# Sheet_1.net
KiCad netlist of a schematic drawn in Altium Designer
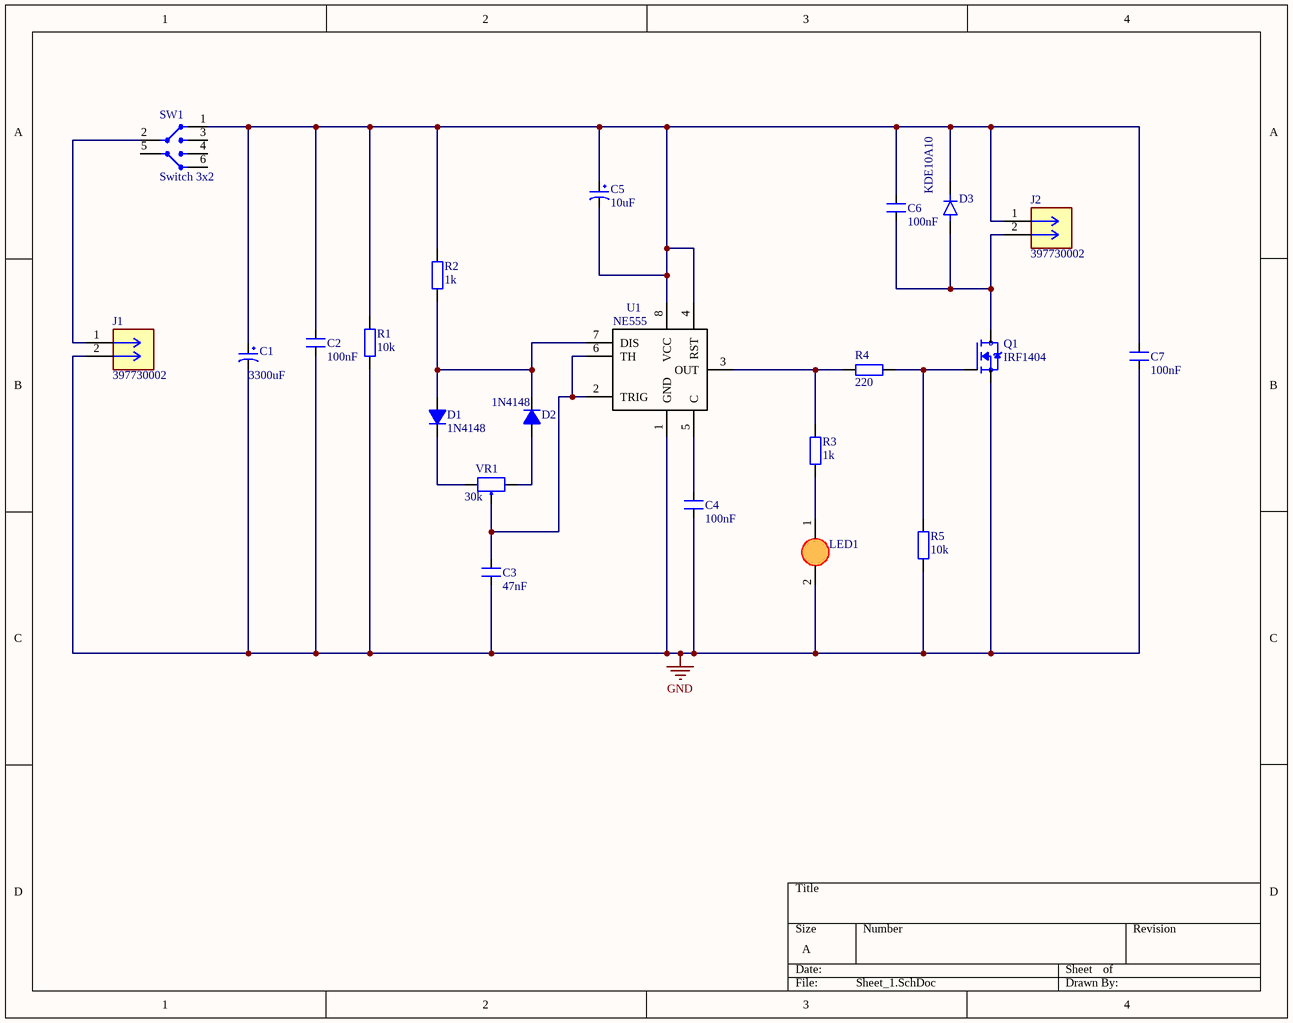
[diagram p0: Sheet_1.SchDoc]

(export (version "E")
  (design (tool "Eeschema 10.0.6"))
  (components
    (comp (ref "C1")
      (value "3300uF")
      (footprint "CP1.5/3.4")
      (description "Cap 100uF/35V - 470uF/16V")
      (libsource (lib "Cty1") (part "CP3"))
    )
    (comp (ref "C2")
      (value "100nF")
      (footprint "CN1.5")
      (libsource (lib "KhanhBK_SCH_Library_1") (part "CN"))
    )
    (comp (ref "C3") (value "47nF") (footprint "CN1.5") (libsource (lib "KhanhBK_SCH_Library_1") (part "CN")))
    (comp (ref "C4")
      (value "100nF")
      (footprint "CN1.5")
      (libsource (lib "KhanhBK_SCH_Library_1") (part "CN"))
    )
    (comp (ref "C5")
      (value "10uF")
      (footprint "CP1/2")
      (description "Cap P  0,1uF < 22uF , 16 - 50V")
      (libsource (lib "Cty1") (part "CP1"))
    )
    (comp (ref "C6")
      (value "100nF")
      (footprint "CN1.5")
      (libsource (lib "KhanhBK_SCH_Library_1") (part "CN"))
    )
    (comp (ref "C7")
      (value "100nF")
      (footprint "CN1.5")
      (libsource (lib "KhanhBK_SCH_Library_1") (part "CN"))
    )
    (comp (ref "D1")
      (value "1N4148")
      (footprint "D0.5A")
      (description "D0.5A")
      (libsource (lib "Cty1") (part "D0.5A"))
    )
    (comp (ref "D2")
      (value "1N4148")
      (footprint "D0.5A")
      (description "D0.5A")
      (libsource (lib "Cty1") (part "D0.5A"))
    )
    (comp (ref "D3")
      (value "KDE10A10")
      (footprint "DIOAD1990W125L900D530")
      (description "3A, 200V, Schottky Rectifier")
      (fields (field (name "MF") "Taiwan Semiconductor") (field (name "MP") "SR320"))
      (libsource (lib "SR320") (part "SR320"))
    )
    (comp (ref "J1")
      (value "397730002")
      (footprint "CONN_39773-0002_MOL")
      (description "2 Position Wire to Board Terminal Block Horizontal with Board 0.100 (2.54mm) Through Hole")
      (fields (field (name "MF") "Molex"))
      (libsource (lib "397730002") (part "397730002"))
    )
    (comp (ref "J2")
      (value "397730002")
      (footprint "CONN_39773-0002_MOL")
      (description "2 Position Wire to Board Terminal Block Horizontal with Board 0.100 (2.54mm) Through Hole")
      (fields (field (name "MF") "Molex"))
      (libsource (lib "397730002") (part "397730002"))
    )
    (comp (ref "LED1")
      (value "LED5")
      (footprint "LED-5 GRe")
      (description "LED 5mm")
      (libsource (lib "Cty1") (part "LED 5mm"))
    )
    (comp (ref "Q1")
      (value "IRF1404")
      (footprint "TO254P1016X419X2286-3")
      (description "N-Channel 55 V 49A (Tc) 94W (Tc) Through Hole TO-220AB")
      (fields (field (name "MP") "IRFZ44N") (field (name "MF") "Infineon Technologies"))
      (libsource (lib "IRFZ44N") (part "IRFZ44N"))
    )
    (comp (ref "R1")
      (value "10k")
      (footprint "R1/4W")
      (description "Resistor 1/4W")
      (libsource (lib "Cty1") (part "R1/4W"))
    )
    (comp (ref "R2")
      (value "1k")
      (footprint "R1/4W")
      (description "Resistor 1/4W")
      (libsource (lib "Cty1") (part "R1/4W"))
    )
    (comp (ref "R3")
      (value "1k")
      (footprint "R1/4W")
      (description "Resistor 1/4W")
      (libsource (lib "Cty1") (part "R1/4W"))
    )
    (comp (ref "R4")
      (value "220")
      (footprint "R1/4W")
      (description "Resistor 1/4W")
      (libsource (lib "Cty1") (part "R1/4W"))
    )
    (comp (ref "R5")
      (value "10k")
      (footprint "R1/4W")
      (description "Resistor 1/4W")
      (libsource (lib "Cty1") (part "R1/4W"))
    )
    (comp (ref "SW1")
      (value "Switch 3x2")
      (footprint "SW3-DIP")
      (libsource (lib "KhanhBK_SCH_Library_1") (part "SW3x2"))
    )
    (comp (ref "U1")
      (value "NE555")
      (footprint "DIP8")
      (description "TIMER IC")
      (fields
        (field (name "MANUFACTURER PART NUMBER") "NE555DT")
        (field (name "MANUFACTURER") "STMicroelectronics")
      )
      (libsource (lib "KhanhBK_SCH_Library_1") (part "NE555"))
    )
    (comp (ref "VR1")
      (value "30k")
      (footprint "VOL_1")
      (description "Var Resistor")
      (libsource (lib "Cty1") (part "Var Resitor"))
    )
  )
  (nets
    (net (code "1") (name "GND") (class "Default")
      (node (ref "C1") (pin "2") (pinfunction "2_2") (pintype "passive"))
      (node (ref "C2") (pin "2") (pinfunction "2_2") (pintype "passive"))
      (node (ref "C3") (pin "1") (pinfunction "1_1") (pintype "passive"))
      (node (ref "C4") (pin "1") (pinfunction "1_1") (pintype "passive"))
      (node (ref "C7") (pin "2") (pinfunction "2_2") (pintype "passive"))
      (node (ref "J1") (pin "2") (pinfunction "2_2") (pintype "passive"))
      (node (ref "LED1") (pin "2") (pinfunction "K_2") (pintype "passive"))
      (node (ref "Q1") (pin "3") (pinfunction "S_3") (pintype "passive"))
      (node (ref "R1") (pin "1") (pinfunction "1_1") (pintype "passive"))
      (node (ref "R5") (pin "1") (pinfunction "1_1") (pintype "passive"))
      (node (ref "U1") (pin "1") (pinfunction "GND_1") (pintype "passive"))
    )
    (net (code "2") (name "Net-(D1-A)") (class "Default")
      (node (ref "D1") (pin "1") (pinfunction "A_1") (pintype "passive"))
      (node (ref "D2") (pin "2") (pinfunction "K_2") (pintype "passive"))
      (node (ref "R2") (pin "1") (pinfunction "1_1") (pintype "passive"))
      (node (ref "U1") (pin "7") (pinfunction "DIS_7") (pintype "passive"))
    )
    (net (code "3") (name "Net-(D1-K)") (class "Default")
      (node (ref "D1") (pin "2") (pinfunction "K_2") (pintype "passive"))
      (node (ref "VR1") (pin "3") (pinfunction "3_3") (pintype "passive"))
    )
    (net (code "4") (name "Net-(D2-A)") (class "Default")
      (node (ref "D2") (pin "1") (pinfunction "A_1") (pintype "passive"))
      (node (ref "VR1") (pin "1") (pinfunction "1_1") (pintype "passive"))
    )
    (net (code "5") (name "Net-(D3-K)") (class "Default")
      (node (ref "C1") (pin "1") (pinfunction "1_1") (pintype "passive"))
      (node (ref "C2") (pin "1") (pinfunction "1_1") (pintype "passive"))
      (node (ref "C5") (pin "1") (pinfunction "1_1") (pintype "passive"))
      (node (ref "C5") (pin "2") (pinfunction "2_2") (pintype "passive"))
      (node (ref "C6") (pin "2") (pinfunction "2_2") (pintype "passive"))
      (node (ref "C7") (pin "1") (pinfunction "1_1") (pintype "passive"))
      (node (ref "D3") (pin "C") (pinfunction "K_C") (pintype "passive"))
      (node (ref "J2") (pin "1") (pinfunction "1_1") (pintype "passive"))
      (node (ref "R1") (pin "2") (pinfunction "2_2") (pintype "passive"))
      (node (ref "R2") (pin "2") (pinfunction "2_2") (pintype "passive"))
      (node (ref "SW1") (pin "1") (pintype "passive"))
      (node (ref "U1") (pin "4") (pinfunction "RST_4") (pintype "passive"))
      (node (ref "U1") (pin "8") (pinfunction "VCC_8") (pintype "passive"))
    )
    (net (code "6") (name "Net-(J1-Pad1)") (class "Default")
      (node (ref "J1") (pin "1") (pinfunction "1_1") (pintype "passive"))
      (node (ref "SW1") (pin "2") (pintype "passive"))
    )
    (net (code "7") (name "Net-(LED1-A)") (class "Default")
      (node (ref "LED1") (pin "1") (pinfunction "A_1") (pintype "passive"))
      (node (ref "R3") (pin "1") (pinfunction "1_1") (pintype "passive"))
    )
    (net (code "8") (name "Net-(Q1-D)") (class "Default")
      (node (ref "C6") (pin "1") (pinfunction "1_1") (pintype "passive"))
      (node (ref "D3") (pin "A") (pinfunction "A_A") (pintype "passive"))
      (node (ref "J2") (pin "2") (pinfunction "2_2") (pintype "passive"))
      (node (ref "Q1") (pin "2") (pinfunction "D_2") (pintype "passive"))
    )
    (net (code "9") (name "Net-(Q1-G)") (class "Default")
      (node (ref "Q1") (pin "1") (pinfunction "G_1") (pintype "passive"))
      (node (ref "R4") (pin "1") (pinfunction "1_1") (pintype "passive"))
      (node (ref "R5") (pin "2") (pinfunction "2_2") (pintype "passive"))
    )
    (net (code "10") (name "Net-(U1-C)") (class "Default")
      (node (ref "C4") (pin "2") (pinfunction "2_2") (pintype "passive"))
      (node (ref "U1") (pin "5") (pinfunction "C_5") (pintype "passive"))
    )
    (net (code "11") (name "Net-(U1-OUT)") (class "Default")
      (node (ref "R3") (pin "2") (pinfunction "2_2") (pintype "passive"))
      (node (ref "R4") (pin "2") (pinfunction "2_2") (pintype "passive"))
      (node (ref "U1") (pin "3") (pinfunction "OUT_3") (pintype "passive"))
    )
    (net (code "12") (name "Net-(U1-TH)") (class "Default")
      (node (ref "C3") (pin "2") (pinfunction "2_2") (pintype "passive"))
      (node (ref "U1") (pin "2") (pinfunction "TRIG_2") (pintype "passive"))
      (node (ref "U1") (pin "6") (pinfunction "TH_6") (pintype "passive"))
      (node (ref "VR1") (pin "2") (pinfunction "2_2") (pintype "passive"))
    )
    (net (code "13") (name "unconnected-(SW1-6-Pad5)") (class "Default")
      (node (ref "SW1") (pin "5") (pinfunction "6_5") (pintype "passive"))
    )
    (net (code "14") (name "unconnected-(SW1-I{slash}O2-Pad3)") (class "Default")
      (node (ref "SW1") (pin "3") (pinfunction "I/O2_3") (pintype "passive"))
    )
    (net (code "15") (name "unconnected-(SW1-Pad4)") (class "Default")
      (node (ref "SW1") (pin "4") (pintype "passive"))
    )
    (net (code "16") (name "unconnected-(SW1-Pad6)") (class "Default")
      (node (ref "SW1") (pin "6") (pintype "passive"))
    )
  )
)
